# 5V_Digital_Out.net
KiCad netlist of a schematic drawn in Altium Designer
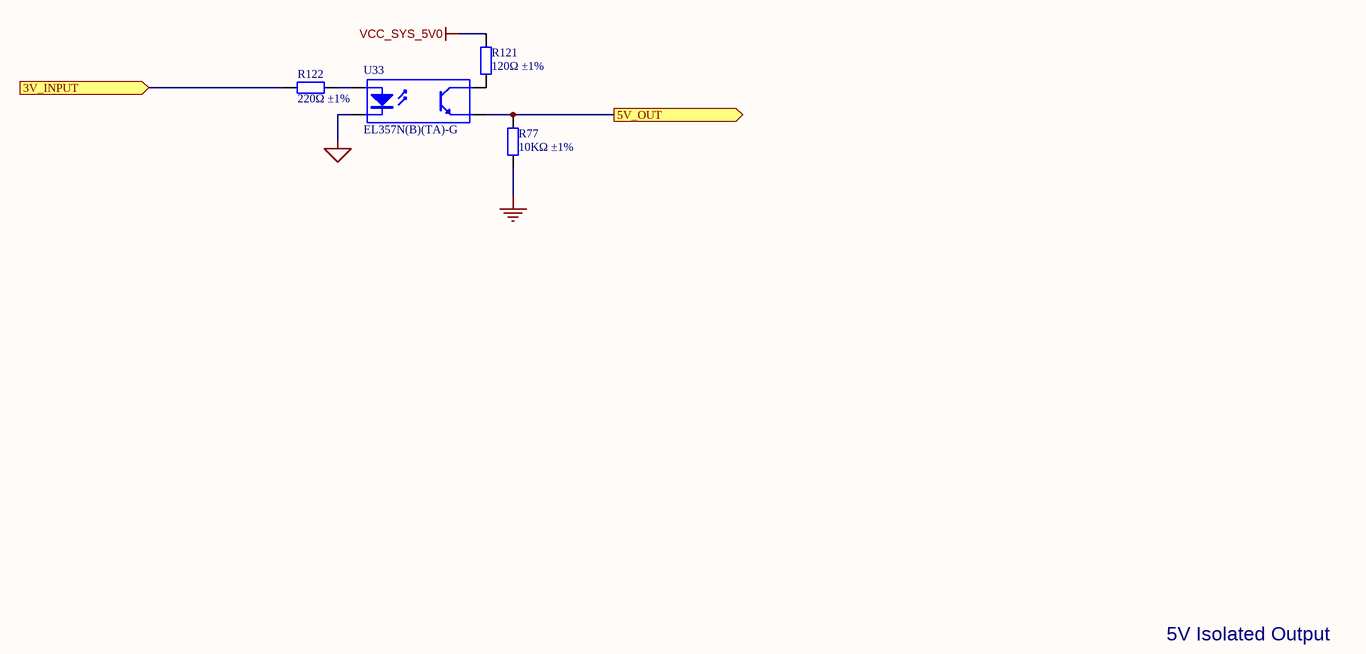
[diagram p0: 5V_Digital_Out.SchDoc]

(export (version "E")
  (design (tool "Eeschema 10.0.6"))
  (components
    (comp (ref "R77")
      (value "10KΩ ±1%")
      (footprint "0402_R")
      (description "Chip resistor")
      (fields
        (field (name "MANUFACTURER") "Uniroyal Elec")
        (field (name "MANUFACTURER PART NUMBER") "0402WGF1002TCE")
      )
      (libsource (lib "RES") (part "0402 10K (1002) 1%"))
    )
    (comp (ref "R121")
      (value "120Ω ±1%")
      (footprint "0402_R")
      (description "Chip resistor")
      (fields
        (field (name "MANUFACTURER") "Uniroyal Elec")
        (field (name "MANUFACTURER PART NUMBER") "0402WGF1200TCE")
      )
      (libsource (lib "RES") (part "0402 120R (1200) 1%"))
    )
    (comp (ref "R122")
      (value "220Ω ±1%")
      (footprint "0402_R")
      (description "Chip resistor")
      (fields
        (field (name "MANUFACTURER") "Uniroyal Elec")
        (field (name "MANUFACTURER PART NUMBER") "0402WGF2200TCE")
      )
      (libsource (lib "RES") (part "0402 220R (2200) 1%"))
    )
    (comp (ref "U33")
      (value "EL357N(B)(TA)-G")
      (footprint "Miscellaneous Devices LC:SOP-4_P2.54")
      (description "80V 3750V 50mA 0.1V@1mA,20mA 1 6V 1.2V DC SOP-4-2.54mm Optocouplers - Phototransistor Output ROHS")
      (fields (field (name "MANUFACTURER") "Everlight Elec"))
      (libsource (lib "IC") (part "EL357N(B)(TA)-G_[C6649]"))
    )
  )
  (nets
    (net (code "1") (name "/3V_INPUT") (class "Default")
      (node (ref "R122") (pin "1") (pinfunction "1_1") (pintype "passive"))
    )
    (net (code "2") (name "/5V_OUT") (class "Default")
      (node (ref "R77") (pin "2") (pinfunction "2_2") (pintype "passive"))
      (node (ref "U33") (pin "3") (pinfunction "E_3") (pintype "passive"))
    )
    (net (code "3") (name "GND") (class "Default")
      (node (ref "R77") (pin "1") (pinfunction "1_1") (pintype "passive"))
    )
    (net (code "4") (name "MCU_GND") (class "Default")
      (node (ref "U33") (pin "2") (pinfunction "K_2") (pintype "passive"))
    )
    (net (code "5") (name "Net-(U33-A)") (class "Default")
      (node (ref "R122") (pin "2") (pinfunction "2_2") (pintype "passive"))
      (node (ref "U33") (pin "1") (pinfunction "A_1") (pintype "passive"))
    )
    (net (code "6") (name "Net-(U33-C)") (class "Default")
      (node (ref "R121") (pin "2") (pinfunction "2_2") (pintype "passive"))
      (node (ref "U33") (pin "4") (pinfunction "C_4") (pintype "passive"))
    )
    (net (code "7") (name "VCC_SYS_5V0") (class "Default")
      (node (ref "R121") (pin "1") (pinfunction "1_1") (pintype "passive"))
    )
  )
)
